# SCH_IntegratedAvionics_Mk_1_2024-03-19.net
KiCad netlist of a schematic drawn in EasyEDA
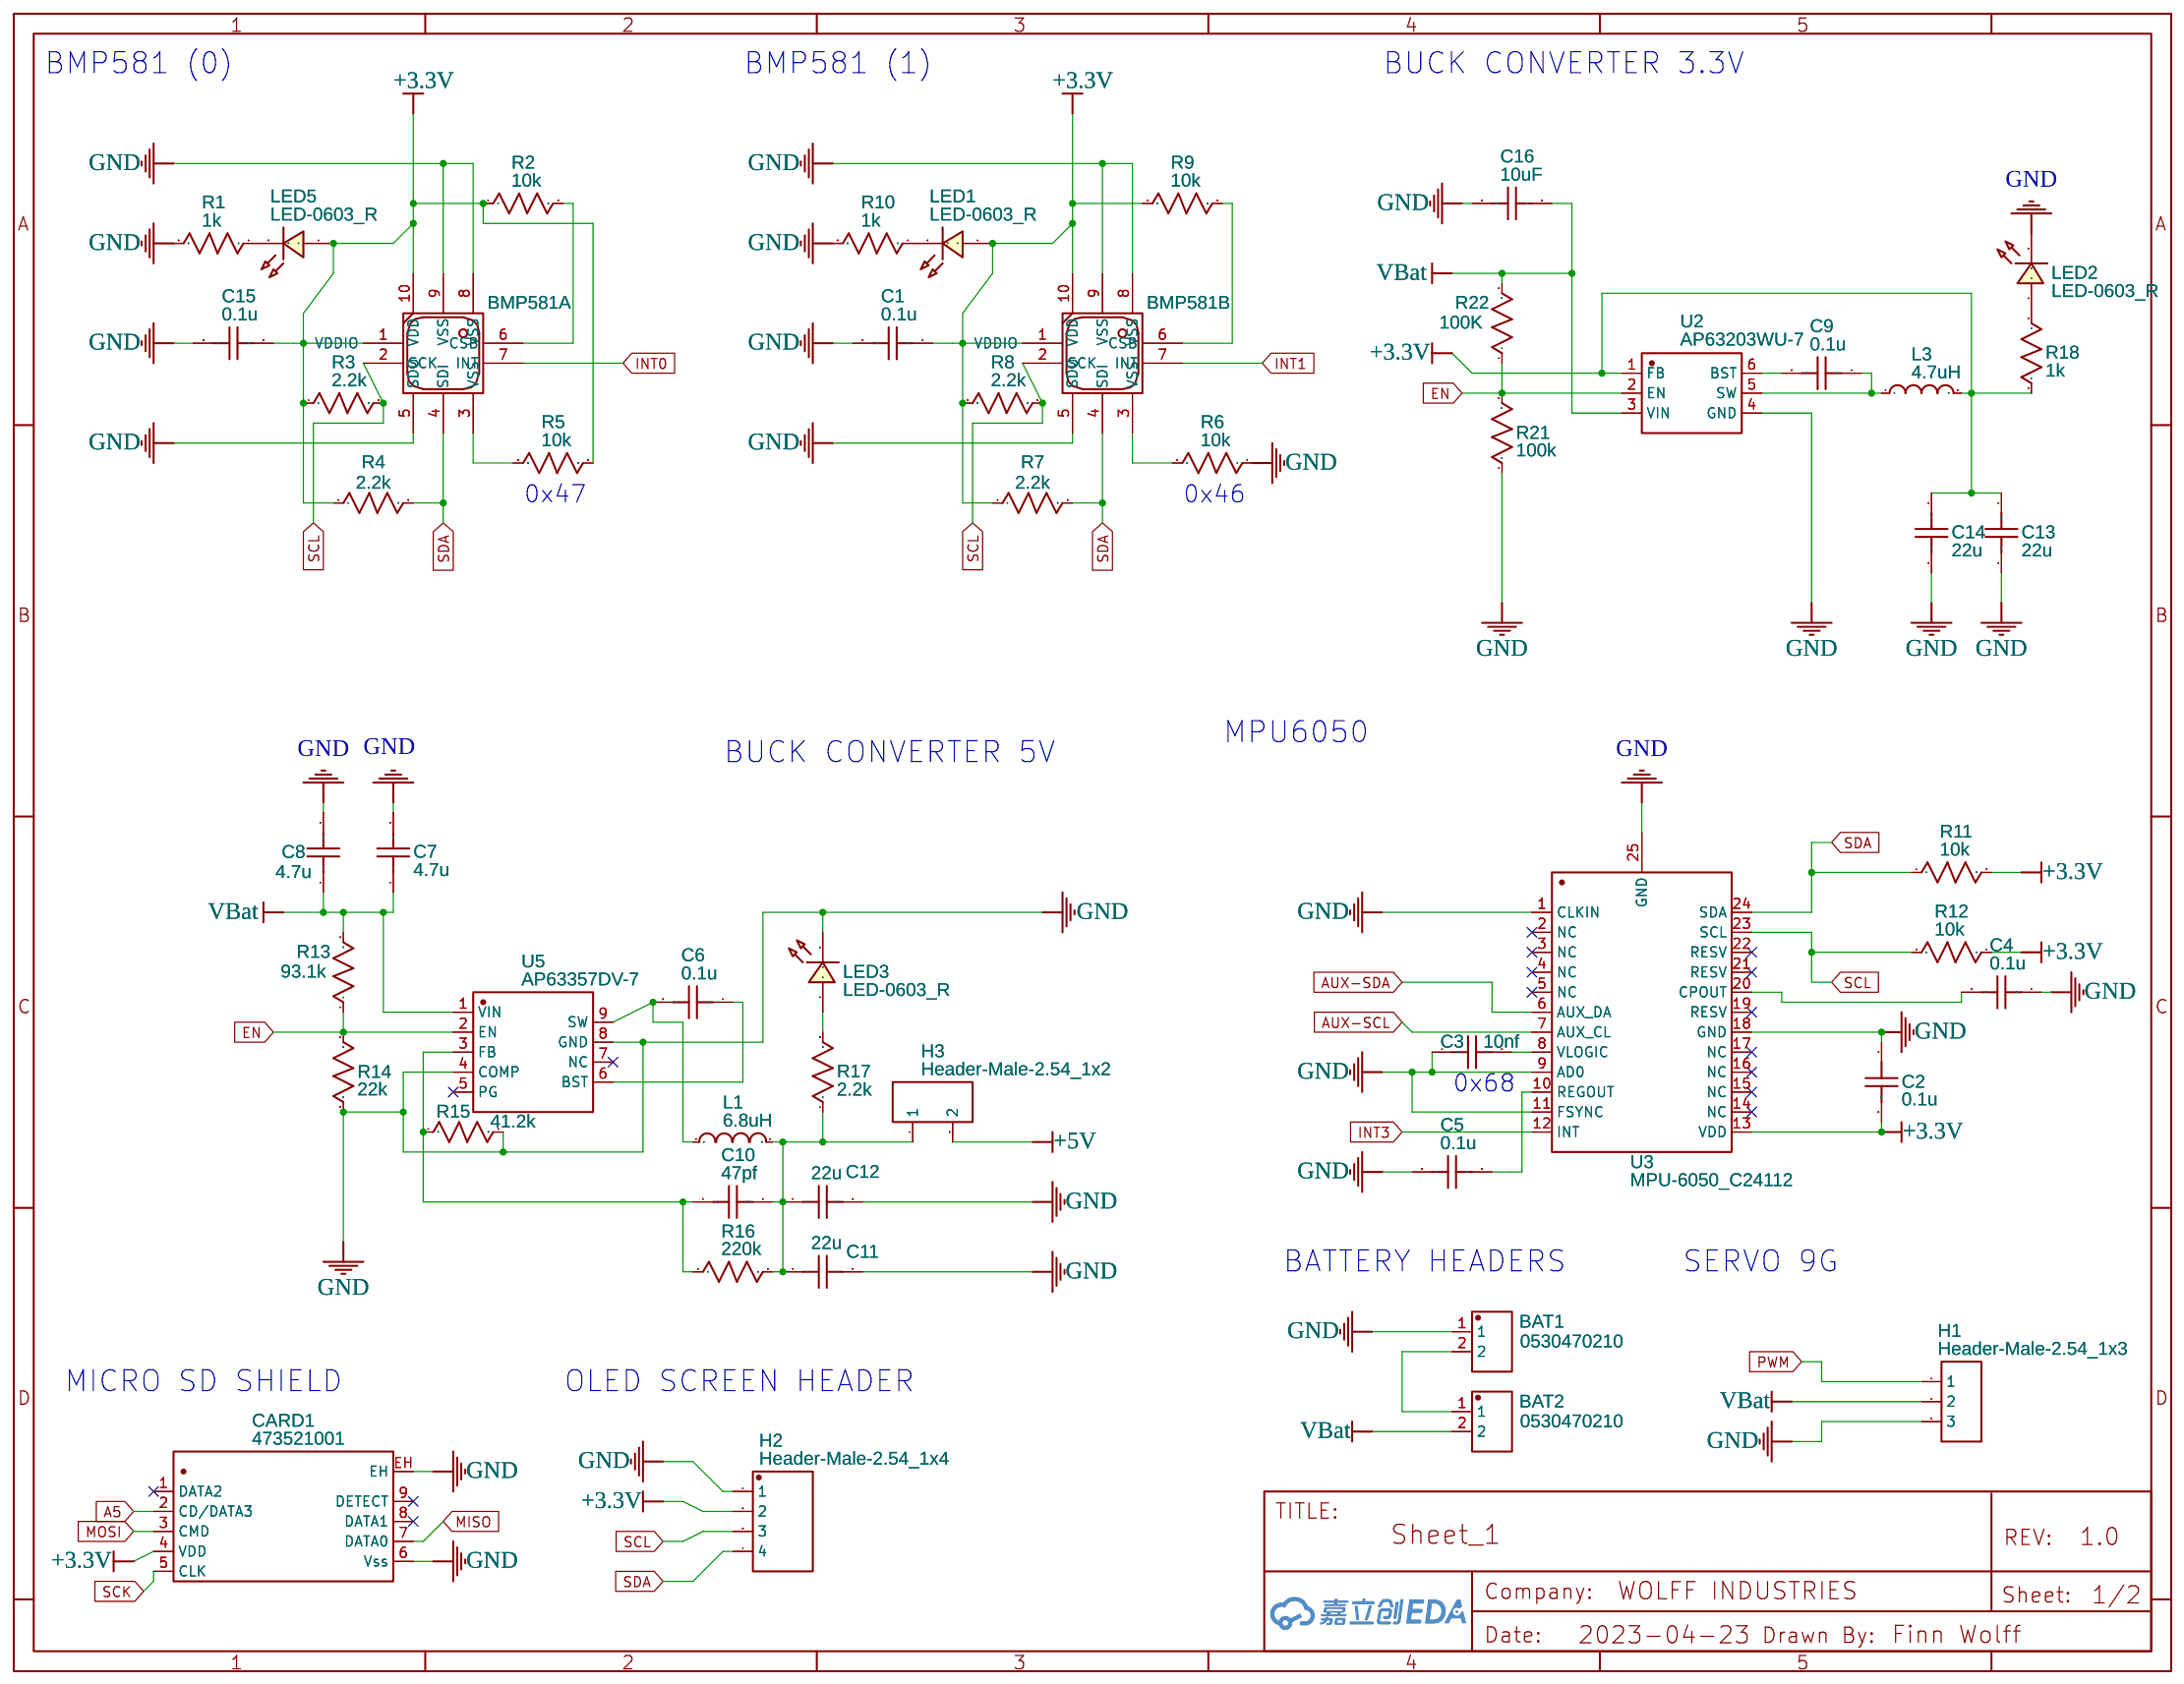
[diagram p0: Sheet_1SEN]
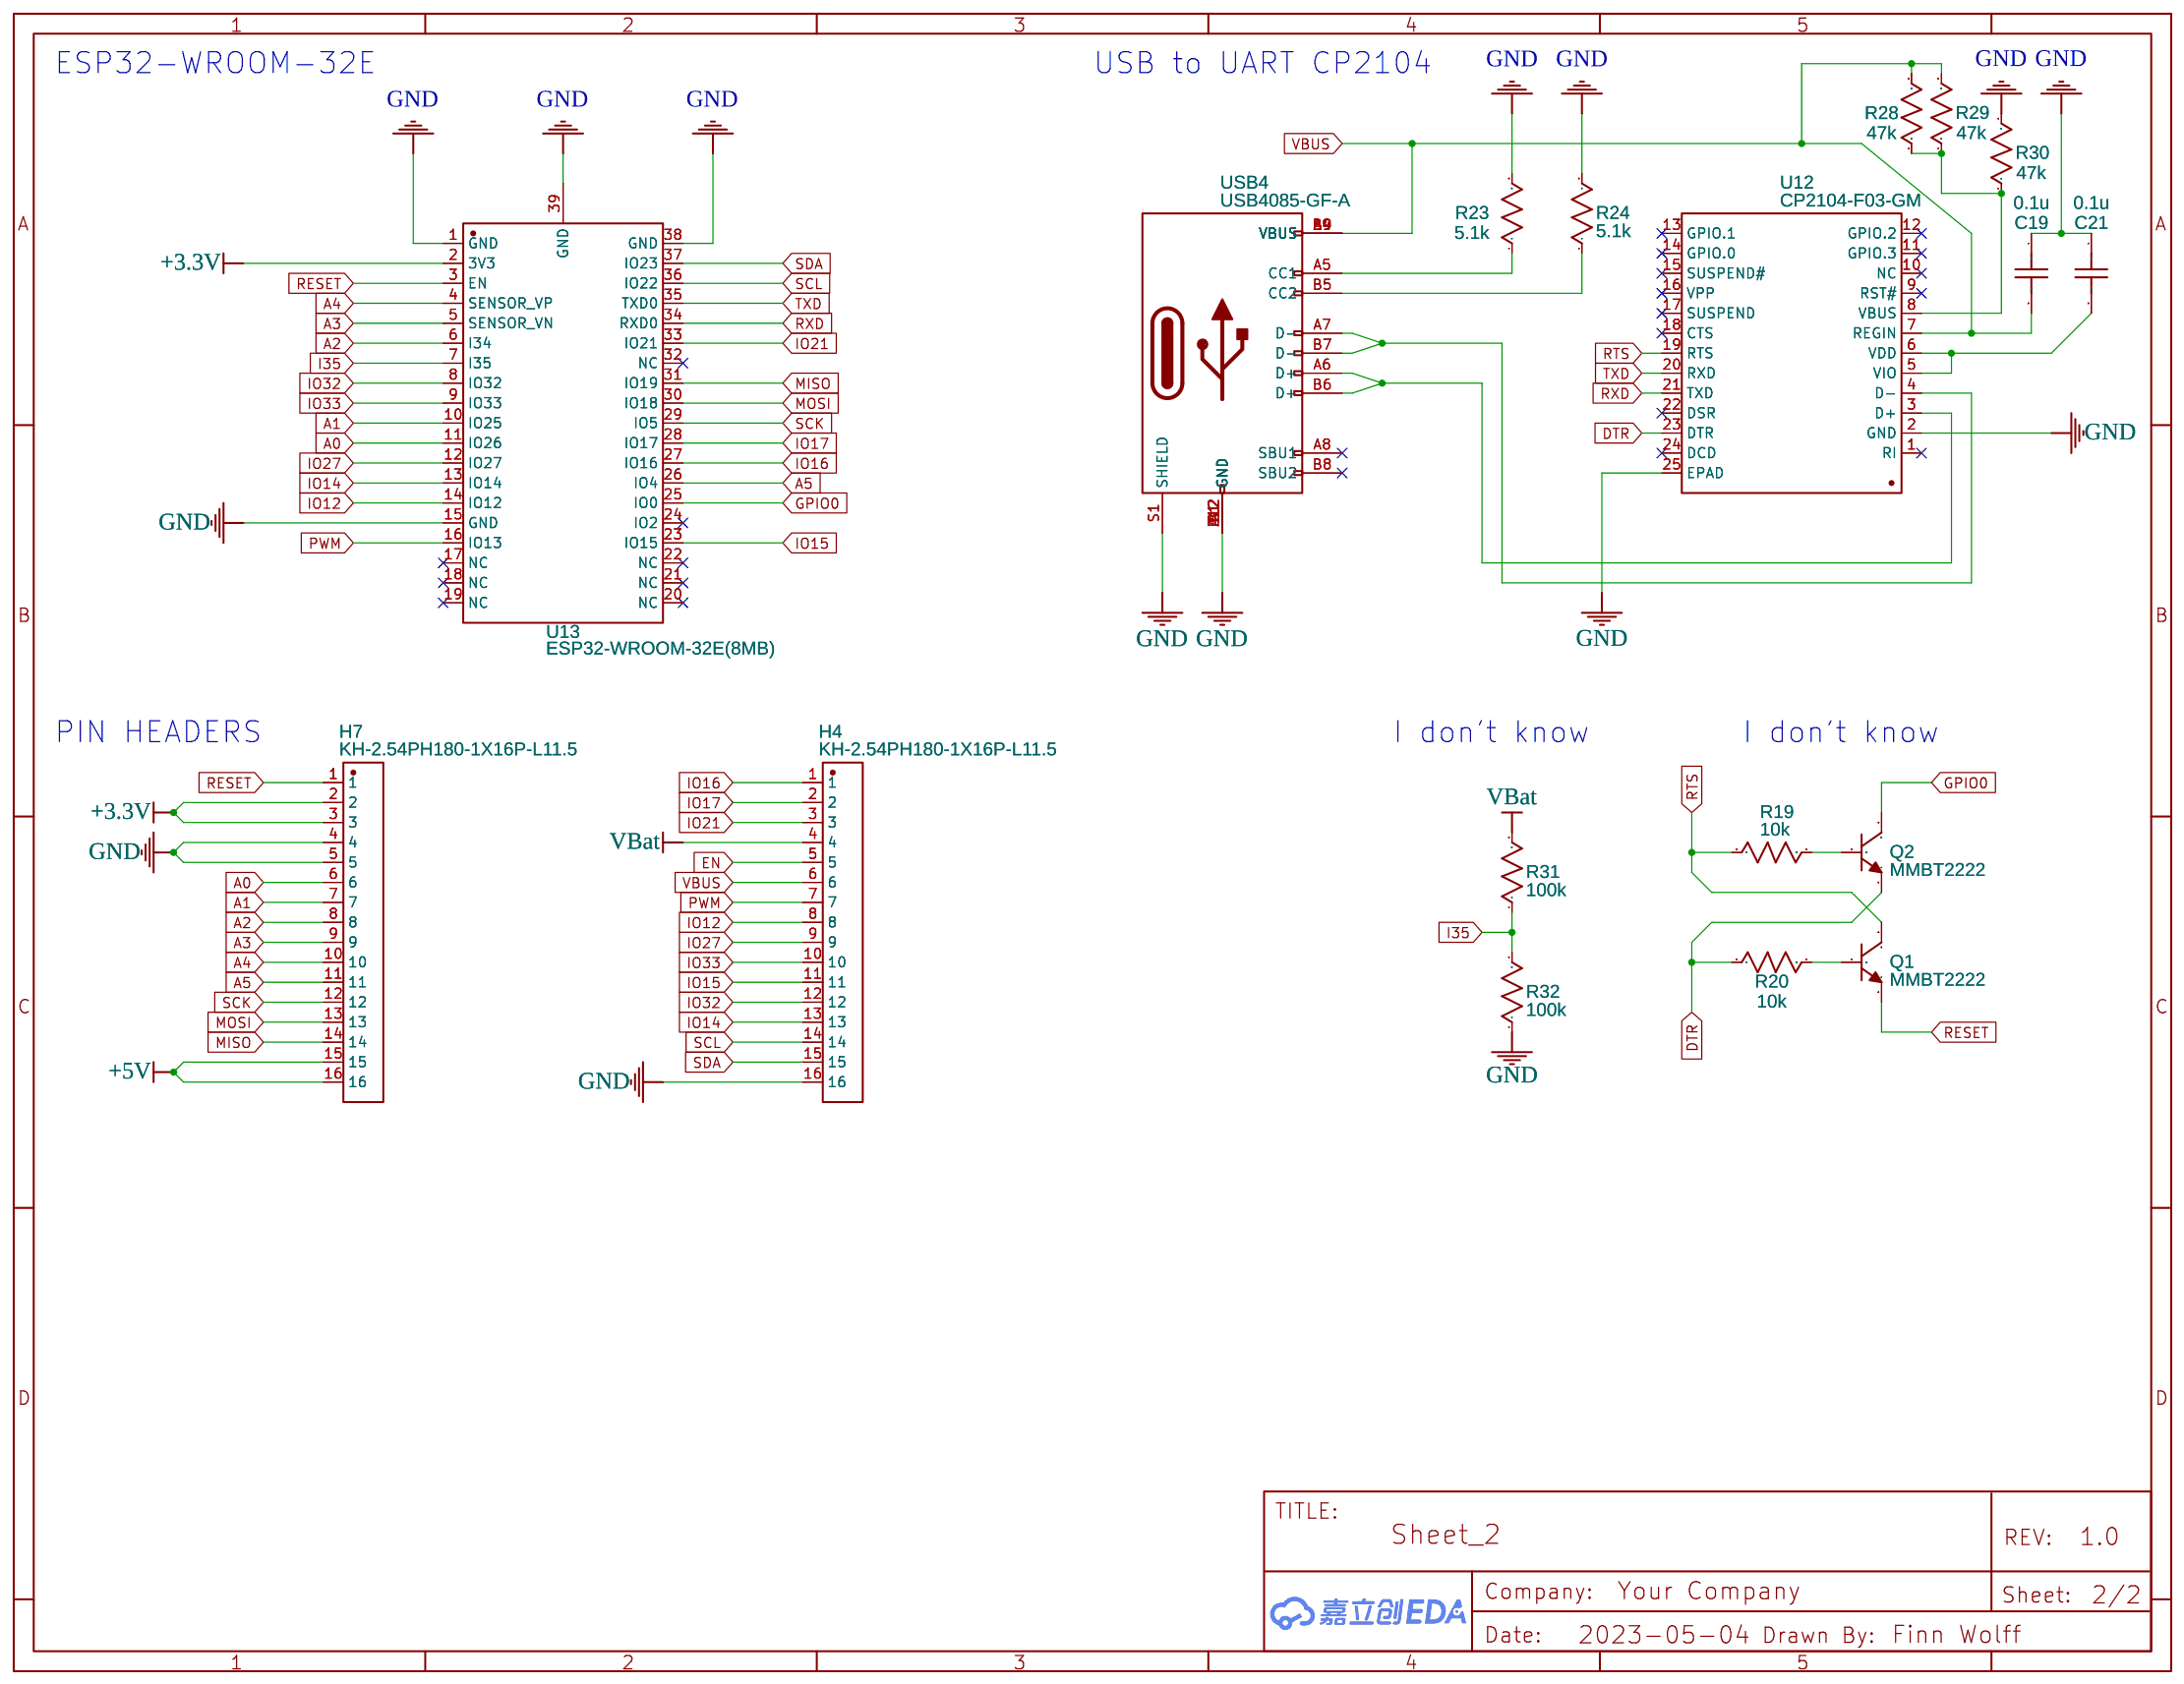
[diagram p1: Sheet_2ESP]

(export (version "E")
  (design (tool "Eeschema 10.0.6"))
  (components
    (comp (ref "BAT1")
      (value "0530470210")
      (fields (field (name "BOM_Supplier Part") "C114130"))
      (libsource (lib "") (part "0530470210"))
    )
    (comp (ref "BAT2")
      (value "0530470210")
      (fields (field (name "BOM_Supplier Part") "C114130"))
      (libsource (lib "") (part "0530470210"))
    )
    (comp (ref "C1")
      (value "0.1u")
      (fields (field (name "Manufacturer Part") "0402B104K160CT"))
      (libsource (lib "") (part "0402B104K160CT"))
    )
    (comp (ref "C2")
      (value "0.1u")
      (fields (field (name "Manufacturer Part") "0402B104K160CT"))
      (libsource (lib "") (part "0402B104K160CT_1"))
    )
    (comp (ref "C3") (value "10nf") (libsource (lib "") (part "C_0603_US")))
    (comp (ref "C4")
      (value "0.1u")
      (fields (field (name "Manufacturer Part") "0402B104K160CT"))
      (libsource (lib "") (part "0402B104K160CT"))
    )
    (comp (ref "C5")
      (value "0.1u")
      (fields (field (name "Manufacturer Part") "0402B104K160CT"))
      (libsource (lib "") (part "0402B104K160CT"))
    )
    (comp (ref "C6")
      (value "0.1u")
      (fields (field (name "Manufacturer Part") "0402B104K160CT"))
      (libsource (lib "") (part "0402B104K160CT"))
    )
    (comp (ref "C7") (value "4.7u") (libsource (lib "") (part "C_0603_US_2")))
    (comp (ref "C8") (value "4.7u") (libsource (lib "") (part "C_0603_US_2")))
    (comp (ref "C9")
      (value "0.1u")
      (fields (field (name "Manufacturer Part") "0402B104K160CT"))
      (libsource (lib "") (part "0402B104K160CT"))
    )
    (comp (ref "C10") (value "47pf") (libsource (lib "") (part "C_0603_US")))
    (comp (ref "C11") (value "22u") (libsource (lib "") (part "C_0603_US")))
    (comp (ref "C12") (value "22u") (libsource (lib "") (part "C_0603_US")))
    (comp (ref "C13") (value "22u") (libsource (lib "") (part "C_0603_US_1")))
    (comp (ref "C14") (value "22u") (libsource (lib "") (part "C_0603_US_1")))
    (comp (ref "C15")
      (value "0.1u")
      (fields (field (name "Manufacturer Part") "0402B104K160CT"))
      (libsource (lib "") (part "0402B104K160CT"))
    )
    (comp (ref "C16")
      (value "10uF")
      (fields
        (field (name "Manufacturer Part") "CL32A106KA9LNNE")
        (field (name "Manufacturer") "SAMSUNG(三星)")
      )
      (libsource (lib "") (part "CL32A106KA9LNNE"))
    )
    (comp (ref "CARD1")
      (value "473521001")
      (fields (field (name "BOM_Supplier Part") "C293569"))
      (libsource (lib "") (part "473521001"))
    )
    (comp (ref "H1")
      (value "Header-Male-2.54_1x3")
      (fields (field (name "BOM_Manufacturer Part") "2.54-1*3P针") (field (name "BOM_Supplier Part") "C49257"))
      (libsource (lib "") (part "Header-Male-2.54_1x3"))
    )
    (comp (ref "H2")
      (value "Header-Male-2.54_1x4")
      (fields
        (field (name "BOM_Manufacturer Part") "B-2100S04P-A110")
        (field (name "BOM_Supplier Part") "C124378")
      )
      (libsource (lib "") (part "Header-Male-2.54_1x4"))
    )
    (comp (ref "H3")
      (value "Header-Male-2.54_1x2")
      (fields (field (name "BOM_Manufacturer Part") "826629-2") (field (name "BOM_Supplier Part") "C86471"))
      (libsource (lib "") (part "Header-Male-2.54_1x2"))
    )
    (comp (ref "L1")
      (value "6.8uH")
      (fields
        (field (name "Manufacturer Part") "HPC5040NF-6R8M")
        (field (name "Manufacturer") "TAI-TECH(台庆)")
      )
      (libsource (lib "") (part "HPC5040NF-6R8M"))
    )
    (comp (ref "L3")
      (value "4.7uH")
      (fields
        (field (name "Manufacturer Part") "NRS5020T4R7MMGJ")
        (field (name "Manufacturer") "TAIYO YUDEN(太诱)")
      )
      (libsource (lib "") (part "NRS5020T4R7MMGJ"))
    )
    (comp (ref "LED1")
      (value "LED-0603_R")
      (fields
        (field (name "BOM_Manufacturer Part") "19-217/R6C-AL1M2VY/3T")
        (field (name "BOM_Supplier Part") "C72044")
      )
      (libsource (lib "") (part "LED-0603_R"))
    )
    (comp (ref "LED2")
      (value "LED-0603_R")
      (fields
        (field (name "BOM_Manufacturer Part") "19-217/R6C-AL1M2VY/3T")
        (field (name "BOM_Supplier Part") "C72044")
      )
      (libsource (lib "") (part "LED-0603_R_1"))
    )
    (comp (ref "LED3")
      (value "LED-0603_R")
      (fields
        (field (name "BOM_Manufacturer Part") "19-217/R6C-AL1M2VY/3T")
        (field (name "BOM_Supplier Part") "C72044")
      )
      (libsource (lib "") (part "LED-0603_R_1"))
    )
    (comp (ref "LED5")
      (value "LED-0603_R")
      (fields
        (field (name "BOM_Manufacturer Part") "19-217/R6C-AL1M2VY/3T")
        (field (name "BOM_Supplier Part") "C72044")
      )
      (libsource (lib "") (part "LED-0603_R"))
    )
    (comp (ref "R1") (value "1k") (libsource (lib "") (part "R_0603_US_2")))
    (comp (ref "R2") (value "10k") (libsource (lib "") (part "R_0603_US")))
    (comp (ref "R3") (value "2.2k") (libsource (lib "") (part "R_0603_US")))
    (comp (ref "R4") (value "2.2k") (libsource (lib "") (part "R_0603_US")))
    (comp (ref "R5") (value "10k") (libsource (lib "") (part "R_0603_US_2")))
    (comp (ref "R6") (value "10k") (libsource (lib "") (part "R_0603_US_2")))
    (comp (ref "R7") (value "2.2k") (libsource (lib "") (part "R_0603_US")))
    (comp (ref "R8") (value "2.2k") (libsource (lib "") (part "R_0603_US")))
    (comp (ref "R9") (value "10k") (libsource (lib "") (part "R_0603_US")))
    (comp (ref "R10") (value "1k") (libsource (lib "") (part "R_0603_US_2")))
    (comp (ref "R11") (value "10k") (libsource (lib "") (part "R_0603_US")))
    (comp (ref "R12") (value "10k") (libsource (lib "") (part "R_0603_US_2")))
    (comp (ref "R13") (value "93.1k") (libsource (lib "") (part "R_0603_US_1")))
    (comp (ref "R14") (value "22k") (libsource (lib "") (part "R_0603_US_1")))
    (comp (ref "R15") (value "41.2k") (libsource (lib "") (part "R_0603_US")))
    (comp (ref "R16") (value "220k") (libsource (lib "") (part "R_0603_US")))
    (comp (ref "R17") (value "2.2k") (libsource (lib "") (part "R_0603_US_1")))
    (comp (ref "R18") (value "1k") (libsource (lib "") (part "R_0603_US_1")))
    (comp (ref "R21") (value "100k") (libsource (lib "") (part "R_0603_US_1")))
    (comp (ref "R22") (value "100K") (libsource (lib "") (part "R_0603_US_1")))
    (comp (ref "U1")
      (value "BMP581A")
      (fields
        (field (name "BOM_Manufacturer Part") "BMP581")
        (field (name "BOM_Supplier Part") "BMP581CT-ND")
      )
      (libsource (lib "") (part "BMP581"))
    )
    (comp (ref "U2")
      (value "AP63203WU-7")
      (fields (field (name "Manufacturer") "DIODES(美台)"))
      (libsource (lib "") (part "AP63203WU-7"))
    )
    (comp (ref "U3")
      (value "MPU-6050_C24112")
      (fields (field (name "BOM_Manufacturer Part") "MPU-6050") (field (name "BOM_Supplier Part") "C24112"))
      (libsource (lib "") (part "MPU-6050_C24112"))
    )
    (comp (ref "U4")
      (value "BMP581B")
      (fields
        (field (name "BOM_Manufacturer Part") "BMP581")
        (field (name "BOM_Supplier Part") "BMP581CT-ND")
      )
      (libsource (lib "") (part "BMP581"))
    )
    (comp (ref "U5")
      (value "AP63357DV-7")
      (fields (field (name "BOM_Supplier Part") "C2158014"))
      (libsource (lib "") (part "AP63357DV-7"))
    )
    (comp (ref "C19") (value "0.1u") (libsource (lib "") (part "C_0603_US")))
    (comp (ref "C21") (value "0.1u") (libsource (lib "") (part "C_0603_US")))
    (comp (ref "H4")
      (value "KH-2.54PH180-1X16P-L11.5")
      (fields (field (name "Manufacturer") "kinghelm(金航标)"))
      (libsource (lib "") (part "KH-2.54PH180-1X16P-L11.5"))
    )
    (comp (ref "H7")
      (value "KH-2.54PH180-1X16P-L11.5")
      (fields (field (name "Manufacturer") "kinghelm(金航标)"))
      (libsource (lib "") (part "KH-2.54PH180-1X16P-L11.5"))
    )
    (comp (ref "Q1")
      (value "MMBT2222")
      (fields (field (name "Manufacturer") "YONGYUTAI(永裕泰)"))
      (libsource (lib "") (part "MMBT2222"))
    )
    (comp (ref "Q2")
      (value "MMBT2222")
      (fields (field (name "Manufacturer") "YONGYUTAI(永裕泰)"))
      (libsource (lib "") (part "MMBT2222"))
    )
    (comp (ref "R19") (value "10k") (libsource (lib "") (part "R_0603_US")))
    (comp (ref "R20") (value "10k") (libsource (lib "") (part "R_0603_US")))
    (comp (ref "R23") (value "5.1k") (libsource (lib "") (part "R_0603_US_1")))
    (comp (ref "R24") (value "5.1k") (libsource (lib "") (part "R_0603_US_1")))
    (comp (ref "R28") (value "47k") (libsource (lib "") (part "R_0603_US_1")))
    (comp (ref "R29") (value "47k") (libsource (lib "") (part "R_0603_US_1")))
    (comp (ref "R30") (value "47k") (libsource (lib "") (part "R_0603_US_1")))
    (comp (ref "R31") (value "100k") (libsource (lib "") (part "R_0603_US_1")))
    (comp (ref "R32") (value "100k") (libsource (lib "") (part "R_0603_US_1")))
    (comp (ref "U12")
      (value "CP2104-F03-GM")
      (fields
        (field (name "BOM_Manufacturer Part") "CP2104-F03-GMR")
        (field (name "BOM_Supplier Part") "C47742")
      )
      (libsource (lib "") (part "CP2104-F03-GM"))
    )
    (comp (ref "U13")
      (value "ESP32-WROOM-32E(8MB)")
      (fields
        (field (name "BOM_Manufacturer Part") "ESP32-WROOM-32E-N8")
        (field (name "BOM_Supplier Part") "C701342")
      )
      (libsource (lib "") (part "ESP32-WROOM-32E(8MB)"))
    )
    (comp (ref "USB4")
      (value "USB4085-GF-A")
      (fields (field (name "BOM_Supplier Part") "C9900013983"))
      (libsource (lib "") (part "USB4085-GF-A"))
    )
  )
  (nets
    (net (code "1") (name "+3.3V") (class "Default")
      (node (ref "C1") (pin "1") (pinfunction "1_1") (pintype "unspecified"))
      (node (ref "C13") (pin "1") (pinfunction "1_1") (pintype "unspecified"))
      (node (ref "C14") (pin "1") (pinfunction "1_1") (pintype "unspecified"))
      (node (ref "C15") (pin "1") (pinfunction "1_1") (pintype "unspecified"))
      (node (ref "C2") (pin "2") (pinfunction "2_2") (pintype "unspecified"))
      (node (ref "CARD1") (pin "4") (pinfunction "VDD_4") (pintype "unspecified"))
      (node (ref "H2") (pin "2") (pinfunction "2_2") (pintype "unspecified"))
      (node (ref "H7") (pin "2") (pinfunction "2_2") (pintype "unspecified"))
      (node (ref "H7") (pin "3") (pinfunction "3_3") (pintype "unspecified"))
      (node (ref "L3") (pin "2") (pinfunction "2_2") (pintype "unspecified"))
      (node (ref "LED1") (pin "1") (pinfunction "1_1") (pintype "unspecified"))
      (node (ref "LED5") (pin "1") (pinfunction "1_1") (pintype "unspecified"))
      (node (ref "R11") (pin "2") (pinfunction "2_2") (pintype "unspecified"))
      (node (ref "R12") (pin "1") (pinfunction "1_1") (pintype "unspecified"))
      (node (ref "R18") (pin "1") (pinfunction "1_1") (pintype "unspecified"))
      (node (ref "R2") (pin "1") (pinfunction "1_1") (pintype "unspecified"))
      (node (ref "R3") (pin "1") (pinfunction "1_1") (pintype "unspecified"))
      (node (ref "R4") (pin "1") (pinfunction "1_1") (pintype "unspecified"))
      (node (ref "R5") (pin "1") (pinfunction "1_1") (pintype "unspecified"))
      (node (ref "R7") (pin "1") (pinfunction "1_1") (pintype "unspecified"))
      (node (ref "R8") (pin "1") (pinfunction "1_1") (pintype "unspecified"))
      (node (ref "R9") (pin "1") (pinfunction "1_1") (pintype "unspecified"))
      (node (ref "U1") (pin "10") (pinfunction "VDD_10") (pintype "unspecified"))
      (node (ref "U13") (pin "2") (pinfunction "3V3_2") (pintype "unspecified"))
      (node (ref "U2") (pin "1") (pinfunction "FB_1") (pintype "unspecified"))
      (node (ref "U3") (pin "13") (pinfunction "VDD_13") (pintype "unspecified"))
      (node (ref "U4") (pin "10") (pinfunction "VDD_10") (pintype "unspecified"))
    )
    (net (code "2") (name "+5V") (class "Default")
      (node (ref "H3") (pin "2") (pinfunction "2_2") (pintype "unspecified"))
      (node (ref "H7") (pin "15") (pinfunction "15_15") (pintype "unspecified"))
      (node (ref "H7") (pin "16") (pinfunction "16_16") (pintype "unspecified"))
    )
    (net (code "3") (name "A0") (class "Default")
      (node (ref "H7") (pin "6") (pinfunction "6_6") (pintype "unspecified"))
      (node (ref "U13") (pin "11") (pinfunction "IO26_11") (pintype "unspecified"))
    )
    (net (code "4") (name "A1") (class "Default")
      (node (ref "H7") (pin "7") (pinfunction "7_7") (pintype "unspecified"))
      (node (ref "U13") (pin "10") (pinfunction "IO25_10") (pintype "unspecified"))
    )
    (net (code "5") (name "A2") (class "Default")
      (node (ref "H7") (pin "8") (pinfunction "8_8") (pintype "unspecified"))
      (node (ref "U13") (pin "6") (pinfunction "I34_6") (pintype "unspecified"))
    )
    (net (code "6") (name "A3") (class "Default")
      (node (ref "H7") (pin "9") (pinfunction "9_9") (pintype "unspecified"))
      (node (ref "U13") (pin "5") (pinfunction "SENSOR_VN_5") (pintype "unspecified"))
    )
    (net (code "7") (name "A4") (class "Default")
      (node (ref "H7") (pin "10") (pinfunction "10_10") (pintype "unspecified"))
      (node (ref "U13") (pin "4") (pinfunction "SENSOR_VP_4") (pintype "unspecified"))
    )
    (net (code "8") (name "A5") (class "Default")
      (node (ref "CARD1") (pin "2") (pinfunction "CD/DATA3_2") (pintype "unspecified"))
      (node (ref "H7") (pin "11") (pinfunction "11_11") (pintype "unspecified"))
      (node (ref "U13") (pin "26") (pinfunction "IO4_26") (pintype "unspecified"))
    )
    (net (code "9") (name "AUX-SCL") (class "Default")
      (node (ref "U3") (pin "7") (pinfunction "AUX_CL_7") (pintype "unspecified"))
    )
    (net (code "10") (name "AUX-SDA") (class "Default")
      (node (ref "U3") (pin "6") (pinfunction "AUX_DA_6") (pintype "unspecified"))
    )
    (net (code "11") (name "DTR") (class "Default")
      (node (ref "Q2") (pin "2") (pinfunction "E_2") (pintype "input"))
      (node (ref "R20") (pin "1") (pinfunction "1_1") (pintype "unspecified"))
      (node (ref "U12") (pin "23") (pinfunction "DTR_23") (pintype "unspecified"))
    )
    (net (code "12") (name "EN") (class "Default")
      (node (ref "H4") (pin "5") (pinfunction "5_5") (pintype "unspecified"))
      (node (ref "R13") (pin "1") (pinfunction "1_1") (pintype "unspecified"))
      (node (ref "R14") (pin "2") (pinfunction "2_2") (pintype "unspecified"))
      (node (ref "R21") (pin "2") (pinfunction "2_2") (pintype "unspecified"))
      (node (ref "R22") (pin "1") (pinfunction "1_1") (pintype "unspecified"))
      (node (ref "U2") (pin "2") (pinfunction "EN_2") (pintype "unspecified"))
      (node (ref "U5") (pin "2") (pinfunction "EN_2") (pintype "unspecified"))
    )
    (net (code "13") (name "GND") (class "Default")
      (node (ref "BAT1") (pin "1") (pinfunction "1_1") (pintype "unspecified"))
      (node (ref "C1") (pin "2") (pinfunction "2_2") (pintype "unspecified"))
      (node (ref "C11") (pin "2") (pinfunction "2_2") (pintype "unspecified"))
      (node (ref "C12") (pin "2") (pinfunction "2_2") (pintype "unspecified"))
      (node (ref "C13") (pin "2") (pinfunction "2_2") (pintype "unspecified"))
      (node (ref "C14") (pin "2") (pinfunction "2_2") (pintype "unspecified"))
      (node (ref "C15") (pin "2") (pinfunction "2_2") (pintype "unspecified"))
      (node (ref "C16") (pin "2") (pinfunction "2_2") (pintype "unspecified"))
      (node (ref "C19") (pin "1") (pinfunction "1_1") (pintype "unspecified"))
      (node (ref "C2") (pin "1") (pinfunction "1_1") (pintype "unspecified"))
      (node (ref "C21") (pin "1") (pinfunction "1_1") (pintype "unspecified"))
      (node (ref "C3") (pin "1") (pinfunction "1_1") (pintype "unspecified"))
      (node (ref "C4") (pin "1") (pinfunction "1_1") (pintype "unspecified"))
      (node (ref "C5") (pin "2") (pinfunction "2_2") (pintype "unspecified"))
      (node (ref "C7") (pin "2") (pinfunction "2_2") (pintype "unspecified"))
      (node (ref "C8") (pin "2") (pinfunction "2_2") (pintype "unspecified"))
      (node (ref "CARD1") (pin "6") (pinfunction "Vss_6") (pintype "unspecified"))
      (node (ref "CARD1") (pin "EH") (pinfunction "EH_EH") (pintype "unspecified"))
      (node (ref "H1") (pin "3") (pinfunction "3_3") (pintype "input"))
      (node (ref "H2") (pin "1") (pinfunction "1_1") (pintype "unspecified"))
      (node (ref "H4") (pin "16") (pinfunction "16_16") (pintype "unspecified"))
      (node (ref "H7") (pin "4") (pinfunction "4_4") (pintype "unspecified"))
      (node (ref "H7") (pin "5") (pinfunction "5_5") (pintype "unspecified"))
      (node (ref "LED2") (pin "2") (pinfunction "2_2") (pintype "unspecified"))
      (node (ref "LED3") (pin "2") (pinfunction "2_2") (pintype "unspecified"))
      (node (ref "R1") (pin "2") (pinfunction "2_2") (pintype "unspecified"))
      (node (ref "R10") (pin "2") (pinfunction "2_2") (pintype "unspecified"))
      (node (ref "R14") (pin "1") (pinfunction "1_1") (pintype "unspecified"))
      (node (ref "R15") (pin "2") (pinfunction "2_2") (pintype "unspecified"))
      (node (ref "R21") (pin "1") (pinfunction "1_1") (pintype "unspecified"))
      (node (ref "R23") (pin "2") (pinfunction "2_2") (pintype "unspecified"))
      (node (ref "R24") (pin "2") (pinfunction "2_2") (pintype "unspecified"))
      (node (ref "R30") (pin "2") (pinfunction "2_2") (pintype "unspecified"))
      (node (ref "R32") (pin "1") (pinfunction "1_1") (pintype "unspecified"))
      (node (ref "R6") (pin "1") (pinfunction "1_1") (pintype "unspecified"))
      (node (ref "U1") (pin "5") (pinfunction "SDO_5") (pintype "unspecified"))
      (node (ref "U1") (pin "8") (pinfunction "VSS_8") (pintype "unspecified"))
      (node (ref "U1") (pin "9") (pinfunction "VSS_9") (pintype "unspecified"))
      (node (ref "U12") (pin "2") (pinfunction "GND_2") (pintype "unspecified"))
      (node (ref "U12") (pin "25") (pinfunction "EPAD_25") (pintype "unspecified"))
      (node (ref "U13") (pin "1") (pinfunction "GND_1") (pintype "unspecified"))
      (node (ref "U13") (pin "15") (pinfunction "GND_15") (pintype "unspecified"))
      (node (ref "U13") (pin "38") (pinfunction "GND_38") (pintype "unspecified"))
      (node (ref "U13") (pin "39") (pinfunction "GND_39") (pintype "unspecified"))
      (node (ref "U2") (pin "4") (pinfunction "GND_4") (pintype "unspecified"))
      (node (ref "U3") (pin "1") (pinfunction "CLKIN_1") (pintype "unspecified"))
      (node (ref "U3") (pin "11") (pinfunction "FSYNC_11") (pintype "unspecified"))
      (node (ref "U3") (pin "18") (pinfunction "GND_18") (pintype "unspecified"))
      (node (ref "U3") (pin "25") (pinfunction "GND_25") (pintype "unspecified"))
      (node (ref "U3") (pin "9") (pinfunction "AD0_9") (pintype "unspecified"))
      (node (ref "U4") (pin "5") (pinfunction "SDO_5") (pintype "unspecified"))
      (node (ref "U4") (pin "8") (pinfunction "VSS_8") (pintype "unspecified"))
      (node (ref "U4") (pin "9") (pinfunction "VSS_9") (pintype "unspecified"))
      (node (ref "U5") (pin "4") (pinfunction "COMP_4") (pintype "unspecified"))
      (node (ref "U5") (pin "8") (pinfunction "GND_8") (pintype "unspecified"))
      (node (ref "USB4") (pin "A1") (pinfunction "GND_A1") (pintype "bidirectional"))
      (node (ref "USB4") (pin "A12") (pinfunction "GND_A12") (pintype "unspecified"))
      (node (ref "USB4") (pin "B1") (pinfunction "GND_B1") (pintype "unspecified"))
      (node (ref "USB4") (pin "B12") (pinfunction "GND_B12") (pintype "unspecified"))
      (node (ref "USB4") (pin "S1") (pinfunction "SHIELD_S1") (pintype "unspecified"))
    )
    (net (code "14") (name "GPIO0") (class "Default")
      (node (ref "Q2") (pin "3") (pinfunction "C_3") (pintype "input"))
      (node (ref "U13") (pin "25") (pinfunction "IO0_25") (pintype "unspecified"))
    )
    (net (code "15") (name "I35") (class "Default")
      (node (ref "R31") (pin "1") (pinfunction "1_1") (pintype "unspecified"))
      (node (ref "R32") (pin "2") (pinfunction "2_2") (pintype "unspecified"))
      (node (ref "U13") (pin "7") (pinfunction "I35_7") (pintype "unspecified"))
    )
    (net (code "16") (name "INT0") (class "Default")
      (node (ref "U1") (pin "7") (pinfunction "INT_7") (pintype "unspecified"))
    )
    (net (code "17") (name "INT1") (class "Default")
      (node (ref "U4") (pin "7") (pinfunction "INT_7") (pintype "unspecified"))
    )
    (net (code "18") (name "INT3") (class "Default")
      (node (ref "U3") (pin "12") (pinfunction "INT_12") (pintype "unspecified"))
    )
    (net (code "19") (name "IO12") (class "Default")
      (node (ref "H4") (pin "8") (pinfunction "8_8") (pintype "unspecified"))
      (node (ref "U13") (pin "14") (pinfunction "IO12_14") (pintype "unspecified"))
    )
    (net (code "20") (name "IO14") (class "Default")
      (node (ref "H4") (pin "13") (pinfunction "13_13") (pintype "unspecified"))
      (node (ref "U13") (pin "13") (pinfunction "IO14_13") (pintype "unspecified"))
    )
    (net (code "21") (name "IO15") (class "Default")
      (node (ref "H4") (pin "11") (pinfunction "11_11") (pintype "unspecified"))
      (node (ref "U13") (pin "23") (pinfunction "IO15_23") (pintype "unspecified"))
    )
    (net (code "22") (name "IO16") (class "Default")
      (node (ref "H4") (pin "1") (pinfunction "1_1") (pintype "unspecified"))
      (node (ref "U13") (pin "27") (pinfunction "IO16_27") (pintype "unspecified"))
    )
    (net (code "23") (name "IO17") (class "Default")
      (node (ref "H4") (pin "2") (pinfunction "2_2") (pintype "unspecified"))
      (node (ref "U13") (pin "28") (pinfunction "IO17_28") (pintype "unspecified"))
    )
    (net (code "24") (name "IO21") (class "Default")
      (node (ref "H4") (pin "3") (pinfunction "3_3") (pintype "unspecified"))
      (node (ref "U13") (pin "33") (pinfunction "IO21_33") (pintype "unspecified"))
    )
    (net (code "25") (name "IO27") (class "Default")
      (node (ref "H4") (pin "9") (pinfunction "9_9") (pintype "unspecified"))
      (node (ref "U13") (pin "12") (pinfunction "IO27_12") (pintype "unspecified"))
    )
    (net (code "26") (name "IO32") (class "Default")
      (node (ref "H4") (pin "12") (pinfunction "12_12") (pintype "unspecified"))
      (node (ref "U13") (pin "8") (pinfunction "IO32_8") (pintype "unspecified"))
    )
    (net (code "27") (name "IO33") (class "Default")
      (node (ref "H4") (pin "10") (pinfunction "10_10") (pintype "unspecified"))
      (node (ref "U13") (pin "9") (pinfunction "IO33_9") (pintype "unspecified"))
    )
    (net (code "28") (name "MISO") (class "Default")
      (node (ref "CARD1") (pin "7") (pinfunction "DATA0_7") (pintype "unspecified"))
      (node (ref "H7") (pin "14") (pinfunction "14_14") (pintype "unspecified"))
      (node (ref "U13") (pin "31") (pinfunction "IO19_31") (pintype "unspecified"))
    )
    (net (code "29") (name "MOSI") (class "Default")
      (node (ref "CARD1") (pin "3") (pinfunction "CMD_3") (pintype "unspecified"))
      (node (ref "H7") (pin "13") (pinfunction "13_13") (pintype "unspecified"))
      (node (ref "U13") (pin "30") (pinfunction "IO18_30") (pintype "unspecified"))
    )
    (net (code "30") (name "Net-(BAT1-Pad2)") (class "Default")
      (node (ref "BAT1") (pin "2") (pinfunction "2_2") (pintype "unspecified"))
      (node (ref "BAT2") (pin "1") (pinfunction "1_1") (pintype "unspecified"))
    )
    (net (code "31") (name "Net-(C10-Pad2)") (class "Default")
      (node (ref "C10") (pin "2") (pinfunction "2_2") (pintype "unspecified"))
      (node (ref "C11") (pin "1") (pinfunction "1_1") (pintype "unspecified"))
      (node (ref "C12") (pin "1") (pinfunction "1_1") (pintype "unspecified"))
      (node (ref "H3") (pin "1") (pinfunction "1_1") (pintype "unspecified"))
      (node (ref "L1") (pin "2") (pinfunction "2_2") (pintype "unspecified"))
      (node (ref "R16") (pin "2") (pinfunction "2_2") (pintype "unspecified"))
      (node (ref "R17") (pin "1") (pinfunction "1_1") (pintype "unspecified"))
    )
    (net (code "32") (name "Net-(LED1-Pad2)") (class "Default")
      (node (ref "LED1") (pin "2") (pinfunction "2_2") (pintype "unspecified"))
      (node (ref "R10") (pin "1") (pinfunction "1_1") (pintype "unspecified"))
    )
    (net (code "33") (name "Net-(LED2-Pad1)") (class "Default")
      (node (ref "LED2") (pin "1") (pinfunction "1_1") (pintype "unspecified"))
      (node (ref "R18") (pin "2") (pinfunction "2_2") (pintype "unspecified"))
    )
    (net (code "34") (name "Net-(LED3-Pad1)") (class "Default")
      (node (ref "LED3") (pin "1") (pinfunction "1_1") (pintype "unspecified"))
      (node (ref "R17") (pin "2") (pinfunction "2_2") (pintype "unspecified"))
    )
    (net (code "35") (name "Net-(LED5-Pad2)") (class "Default")
      (node (ref "LED5") (pin "2") (pinfunction "2_2") (pintype "unspecified"))
      (node (ref "R1") (pin "1") (pinfunction "1_1") (pintype "unspecified"))
    )
    (net (code "36") (name "Net-(Q1-B)") (class "Default")
      (node (ref "Q1") (pin "1") (pinfunction "B_1") (pintype "input"))
      (node (ref "R20") (pin "2") (pinfunction "2_2") (pintype "unspecified"))
    )
    (net (code "37") (name "Net-(Q2-B)") (class "Default")
      (node (ref "Q2") (pin "1") (pinfunction "B_1") (pintype "input"))
      (node (ref "R19") (pin "2") (pinfunction "2_2") (pintype "unspecified"))
    )
    (net (code "38") (name "Net-(R5-Pad2)") (class "Default")
      (node (ref "R5") (pin "2") (pinfunction "2_2") (pintype "unspecified"))
      (node (ref "U1") (pin "3") (pinfunction "VSS_3") (pintype "unspecified"))
    )
    (net (code "39") (name "Net-(R6-Pad2)") (class "Default")
      (node (ref "R6") (pin "2") (pinfunction "2_2") (pintype "unspecified"))
      (node (ref "U4") (pin "3") (pinfunction "VSS_3") (pintype "unspecified"))
    )
    (net (code "40") (name "Net-(U1-CSB)") (class "Default")
      (node (ref "R2") (pin "2") (pinfunction "2_2") (pintype "unspecified"))
      (node (ref "U1") (pin "6") (pinfunction "CSB_6") (pintype "unspecified"))
    )
    (net (code "41") (name "Net-(U2-BST)") (class "Default")
      (node (ref "C9") (pin "2") (pinfunction "2_2") (pintype "unspecified"))
      (node (ref "U2") (pin "6") (pinfunction "BST_6") (pintype "unspecified"))
    )
    (net (code "42") (name "Net-(U2-SW)") (class "Default")
      (node (ref "C9") (pin "1") (pinfunction "1_1") (pintype "unspecified"))
      (node (ref "L3") (pin "1") (pinfunction "1_1") (pintype "unspecified"))
      (node (ref "U2") (pin "5") (pinfunction "SW_5") (pintype "unspecified"))
    )
    (net (code "43") (name "Net-(U3-CPOUT)") (class "Default")
      (node (ref "C4") (pin "2") (pinfunction "2_2") (pintype "unspecified"))
      (node (ref "U3") (pin "20") (pinfunction "CPOUT_20") (pintype "unspecified"))
    )
    (net (code "44") (name "Net-(U3-REGOUT)") (class "Default")
      (node (ref "C5") (pin "1") (pinfunction "1_1") (pintype "unspecified"))
      (node (ref "U3") (pin "10") (pinfunction "REGOUT_10") (pintype "unspecified"))
    )
    (net (code "45") (name "Net-(U3-VLOGIC)") (class "Default")
      (node (ref "C3") (pin "2") (pinfunction "2_2") (pintype "unspecified"))
      (node (ref "U3") (pin "8") (pinfunction "VLOGIC_8") (pintype "unspecified"))
    )
    (net (code "46") (name "Net-(U4-CSB)") (class "Default")
      (node (ref "R9") (pin "2") (pinfunction "2_2") (pintype "unspecified"))
      (node (ref "U4") (pin "6") (pinfunction "CSB_6") (pintype "unspecified"))
    )
    (net (code "47") (name "Net-(U5-BST)") (class "Default")
      (node (ref "C6") (pin "1") (pinfunction "1_1") (pintype "unspecified"))
      (node (ref "U5") (pin "6") (pinfunction "BST_6") (pintype "unspecified"))
    )
    (net (code "48") (name "Net-(U5-FB)") (class "Default")
      (node (ref "C10") (pin "1") (pinfunction "1_1") (pintype "unspecified"))
      (node (ref "R15") (pin "1") (pinfunction "1_1") (pintype "unspecified"))
      (node (ref "R16") (pin "1") (pinfunction "1_1") (pintype "unspecified"))
      (node (ref "U5") (pin "3") (pinfunction "FB_3") (pintype "unspecified"))
    )
    (net (code "49") (name "Net-(U5-SW)") (class "Default")
      (node (ref "C6") (pin "2") (pinfunction "2_2") (pintype "unspecified"))
      (node (ref "L1") (pin "1") (pinfunction "1_1") (pintype "unspecified"))
      (node (ref "U5") (pin "9") (pinfunction "SW_9") (pintype "unspecified"))
    )
    (net (code "50") (name "Net-(U12-D+)") (class "Default")
      (node (ref "U12") (pin "3") (pinfunction "D+_3") (pintype "unspecified"))
      (node (ref "USB4") (pin "A6") (pinfunction "D+_A6") (pintype "bidirectional"))
      (node (ref "USB4") (pin "B6") (pinfunction "D+_B6") (pintype "bidirectional"))
    )
    (net (code "51") (name "Net-(U12-D-)") (class "Default")
      (node (ref "U12") (pin "4") (pinfunction "D-_4") (pintype "unspecified"))
      (node (ref "USB4") (pin "A7") (pinfunction "D-_A7") (pintype "bidirectional"))
      (node (ref "USB4") (pin "B7") (pinfunction "D-_B7") (pintype "bidirectional"))
    )
    (net (code "52") (name "Net-(U12-VBUS)") (class "Default")
      (node (ref "R28") (pin "1") (pinfunction "1_1") (pintype "unspecified"))
      (node (ref "R29") (pin "1") (pinfunction "1_1") (pintype "unspecified"))
      (node (ref "R30") (pin "1") (pinfunction "1_1") (pintype "unspecified"))
      (node (ref "U12") (pin "8") (pinfunction "VBUS_8") (pintype "unspecified"))
    )
    (net (code "53") (name "Net-(U12-VDD)") (class "Default")
      (node (ref "C21") (pin "2") (pinfunction "2_2") (pintype "unspecified"))
      (node (ref "U12") (pin "5") (pinfunction "VIO_5") (pintype "unspecified"))
      (node (ref "U12") (pin "6") (pinfunction "VDD_6") (pintype "unspecified"))
    )
    (net (code "54") (name "Net-(USB4-CC1)") (class "Default")
      (node (ref "R23") (pin "1") (pinfunction "1_1") (pintype "unspecified"))
      (node (ref "USB4") (pin "A5") (pinfunction "CC1_A5") (pintype "bidirectional"))
    )
    (net (code "55") (name "Net-(USB4-CC2)") (class "Default")
      (node (ref "R24") (pin "1") (pinfunction "1_1") (pintype "unspecified"))
      (node (ref "USB4") (pin "B5") (pinfunction "CC2_B5") (pintype "bidirectional"))
    )
    (net (code "56") (name "PWM") (class "Default")
      (node (ref "H1") (pin "1") (pinfunction "1_1") (pintype "input"))
      (node (ref "H4") (pin "7") (pinfunction "7_7") (pintype "unspecified"))
      (node (ref "U13") (pin "16") (pinfunction "IO13_16") (pintype "unspecified"))
    )
    (net (code "57") (name "RESET") (class "Default")
      (node (ref "H7") (pin "1") (pinfunction "1_1") (pintype "unspecified"))
      (node (ref "Q1") (pin "2") (pinfunction "E_2") (pintype "input"))
      (node (ref "U13") (pin "3") (pinfunction "EN_3") (pintype "unspecified"))
    )
    (net (code "58") (name "RTS") (class "Default")
      (node (ref "Q1") (pin "3") (pinfunction "C_3") (pintype "input"))
      (node (ref "R19") (pin "1") (pinfunction "1_1") (pintype "unspecified"))
      (node (ref "U12") (pin "19") (pinfunction "RTS_19") (pintype "unspecified"))
    )
    (net (code "59") (name "RXD") (class "Default")
      (node (ref "U12") (pin "21") (pinfunction "TXD_21") (pintype "unspecified"))
      (node (ref "U13") (pin "34") (pinfunction "RXD0_34") (pintype "unspecified"))
    )
    (net (code "60") (name "SCK") (class "Default")
      (node (ref "CARD1") (pin "5") (pinfunction "CLK_5") (pintype "unspecified"))
      (node (ref "H7") (pin "12") (pinfunction "12_12") (pintype "unspecified"))
      (node (ref "U13") (pin "29") (pinfunction "IO5_29") (pintype "unspecified"))
    )
    (net (code "61") (name "SCL") (class "Default")
      (node (ref "H2") (pin "3") (pinfunction "3_3") (pintype "unspecified"))
      (node (ref "H4") (pin "14") (pinfunction "14_14") (pintype "unspecified"))
      (node (ref "R12") (pin "2") (pinfunction "2_2") (pintype "unspecified"))
      (node (ref "R3") (pin "2") (pinfunction "2_2") (pintype "unspecified"))
      (node (ref "R8") (pin "2") (pinfunction "2_2") (pintype "unspecified"))
      (node (ref "U1") (pin "2") (pinfunction "SCK_2") (pintype "unspecified"))
      (node (ref "U13") (pin "36") (pinfunction "IO22_36") (pintype "unspecified"))
      (node (ref "U3") (pin "23") (pinfunction "SCL_23") (pintype "unspecified"))
      (node (ref "U4") (pin "2") (pinfunction "SCK_2") (pintype "unspecified"))
    )
    (net (code "62") (name "SDA") (class "Default")
      (node (ref "H2") (pin "4") (pinfunction "4_4") (pintype "unspecified"))
      (node (ref "H4") (pin "15") (pinfunction "15_15") (pintype "unspecified"))
      (node (ref "R11") (pin "1") (pinfunction "1_1") (pintype "unspecified"))
      (node (ref "R4") (pin "2") (pinfunction "2_2") (pintype "unspecified"))
      (node (ref "R7") (pin "2") (pinfunction "2_2") (pintype "unspecified"))
      (node (ref "U1") (pin "4") (pinfunction "SDI_4") (pintype "unspecified"))
      (node (ref "U13") (pin "37") (pinfunction "IO23_37") (pintype "unspecified"))
      (node (ref "U3") (pin "24") (pinfunction "SDA_24") (pintype "unspecified"))
      (node (ref "U4") (pin "4") (pinfunction "SDI_4") (pintype "unspecified"))
    )
    (net (code "63") (name "TXD") (class "Default")
      (node (ref "U12") (pin "20") (pinfunction "RXD_20") (pintype "unspecified"))
      (node (ref "U13") (pin "35") (pinfunction "TXD0_35") (pintype "unspecified"))
    )
    (net (code "64") (name "VBUS") (class "Default")
      (node (ref "C19") (pin "2") (pinfunction "2_2") (pintype "unspecified"))
      (node (ref "H4") (pin "6") (pinfunction "6_6") (pintype "unspecified"))
      (node (ref "R28") (pin "2") (pinfunction "2_2") (pintype "unspecified"))
      (node (ref "R29") (pin "2") (pinfunction "2_2") (pintype "unspecified"))
      (node (ref "U12") (pin "7") (pinfunction "REGIN_7") (pintype "unspecified"))
      (node (ref "USB4") (pin "A4") (pinfunction "VBUS_A4") (pintype "bidirectional"))
      (node (ref "USB4") (pin "A9") (pinfunction "VBUS_A9") (pintype "unspecified"))
      (node (ref "USB4") (pin "B4") (pinfunction "VBUS_B4") (pintype "unspecified"))
      (node (ref "USB4") (pin "B9") (pinfunction "VBUS_B9") (pintype "unspecified"))
    )
    (net (code "65") (name "VBat") (class "Default")
      (node (ref "BAT2") (pin "2") (pinfunction "2_2") (pintype "unspecified"))
      (node (ref "C16") (pin "1") (pinfunction "1_1") (pintype "unspecified"))
      (node (ref "C7") (pin "1") (pinfunction "1_1") (pintype "unspecified"))
      (node (ref "C8") (pin "1") (pinfunction "1_1") (pintype "unspecified"))
      (node (ref "H1") (pin "2") (pinfunction "2_2") (pintype "input"))
      (node (ref "H4") (pin "4") (pinfunction "4_4") (pintype "unspecified"))
      (node (ref "R13") (pin "2") (pinfunction "2_2") (pintype "unspecified"))
      (node (ref "R22") (pin "2") (pinfunction "2_2") (pintype "unspecified"))
      (node (ref "R31") (pin "2") (pinfunction "2_2") (pintype "unspecified"))
      (node (ref "U2") (pin "3") (pinfunction "VIN_3") (pintype "unspecified"))
      (node (ref "U5") (pin "1") (pinfunction "VIN_1") (pintype "unspecified"))
    )
    (net (code "66") (name "unconnected-(CARD1-DATA1-Pad8)") (class "Default")
      (node (ref "CARD1") (pin "8") (pinfunction "DATA1_8") (pintype "unspecified+no_connect"))
    )
    (net (code "67") (name "unconnected-(CARD1-DATA2-Pad1)") (class "Default")
      (node (ref "CARD1") (pin "1") (pinfunction "DATA2_1") (pintype "unspecified+no_connect"))
    )
    (net (code "68") (name "unconnected-(CARD1-DETECT-Pad9)") (class "Default")
      (node (ref "CARD1") (pin "9") (pinfunction "DETECT_9") (pintype "unspecified+no_connect"))
    )
    (net (code "69") (name "unconnected-(U1-VDDIO-Pad1)") (class "Default")
      (node (ref "U1") (pin "1") (pinfunction "VDDIO_1") (pintype "unspecified"))
    )
    (net (code "70") (name "unconnected-(U3-NC-Pad2)") (class "Default")
      (node (ref "U3") (pin "2") (pinfunction "NC_2") (pintype "unspecified+no_connect"))
    )
    (net (code "71") (name "unconnected-(U3-NC-Pad3)") (class "Default")
      (node (ref "U3") (pin "3") (pinfunction "NC_3") (pintype "unspecified+no_connect"))
    )
    (net (code "72") (name "unconnected-(U3-NC-Pad4)") (class "Default")
      (node (ref "U3") (pin "4") (pinfunction "NC_4") (pintype "unspecified+no_connect"))
    )
    (net (code "73") (name "unconnected-(U3-NC-Pad5)") (class "Default")
      (node (ref "U3") (pin "5") (pinfunction "NC_5") (pintype "unspecified+no_connect"))
    )
    (net (code "74") (name "unconnected-(U3-NC-Pad14)") (class "Default")
      (node (ref "U3") (pin "14") (pinfunction "NC_14") (pintype "unspecified+no_connect"))
    )
    (net (code "75") (name "unconnected-(U3-NC-Pad15)") (class "Default")
      (node (ref "U3") (pin "15") (pinfunction "NC_15") (pintype "unspecified+no_connect"))
    )
    (net (code "76") (name "unconnected-(U3-NC-Pad16)") (class "Default")
      (node (ref "U3") (pin "16") (pinfunction "NC_16") (pintype "unspecified+no_connect"))
    )
    (net (code "77") (name "unconnected-(U3-NC-Pad17)") (class "Default")
      (node (ref "U3") (pin "17") (pinfunction "NC_17") (pintype "unspecified+no_connect"))
    )
    (net (code "78") (name "unconnected-(U3-RESV-Pad19)") (class "Default")
      (node (ref "U3") (pin "19") (pinfunction "RESV_19") (pintype "unspecified+no_connect"))
    )
    (net (code "79") (name "unconnected-(U3-RESV-Pad21)") (class "Default")
      (node (ref "U3") (pin "21") (pinfunction "RESV_21") (pintype "unspecified+no_connect"))
    )
    (net (code "80") (name "unconnected-(U3-RESV-Pad22)") (class "Default")
      (node (ref "U3") (pin "22") (pinfunction "RESV_22") (pintype "unspecified+no_connect"))
    )
    (net (code "81") (name "unconnected-(U4-VDDIO-Pad1)") (class "Default")
      (node (ref "U4") (pin "1") (pinfunction "VDDIO_1") (pintype "unspecified"))
    )
    (net (code "82") (name "unconnected-(U5-NC-Pad7)") (class "Default")
      (node (ref "U5") (pin "7") (pinfunction "NC_7") (pintype "unspecified+no_connect"))
    )
    (net (code "83") (name "unconnected-(U5-PG-Pad5)") (class "Default")
      (node (ref "U5") (pin "5") (pinfunction "PG_5") (pintype "unspecified+no_connect"))
    )
    (net (code "84") (name "unconnected-(U12-CTS-Pad18)") (class "Default")
      (node (ref "U12") (pin "18") (pinfunction "CTS_18") (pintype "unspecified+no_connect"))
    )
    (net (code "85") (name "unconnected-(U12-DCD-Pad24)") (class "Default")
      (node (ref "U12") (pin "24") (pinfunction "DCD_24") (pintype "unspecified+no_connect"))
    )
    (net (code "86") (name "unconnected-(U12-DSR-Pad22)") (class "Default")
      (node (ref "U12") (pin "22") (pinfunction "DSR_22") (pintype "unspecified+no_connect"))
    )
    (net (code "87") (name "unconnected-(U12-GPIO.0-Pad14)") (class "Default")
      (node (ref "U12") (pin "14") (pinfunction "GPIO.0_14") (pintype "unspecified+no_connect"))
    )
    (net (code "88") (name "unconnected-(U12-GPIO.1-Pad13)") (class "Default")
      (node (ref "U12") (pin "13") (pinfunction "GPIO.1_13") (pintype "unspecified+no_connect"))
    )
    (net (code "89") (name "unconnected-(U12-GPIO.2-Pad12)") (class "Default")
      (node (ref "U12") (pin "12") (pinfunction "GPIO.2_12") (pintype "unspecified+no_connect"))
    )
    (net (code "90") (name "unconnected-(U12-GPIO.3-Pad11)") (class "Default")
      (node (ref "U12") (pin "11") (pinfunction "GPIO.3_11") (pintype "unspecified+no_connect"))
    )
    (net (code "91") (name "unconnected-(U12-NC-Pad10)") (class "Default")
      (node (ref "U12") (pin "10") (pinfunction "NC_10") (pintype "unspecified+no_connect"))
    )
    (net (code "92") (name "unconnected-(U12-RI-Pad1)") (class "Default")
      (node (ref "U12") (pin "1") (pinfunction "RI_1") (pintype "unspecified+no_connect"))
    )
    (net (code "93") (name "unconnected-(U12-RST#-Pad9)") (class "Default")
      (node (ref "U12") (pin "9") (pinfunction "RST#_9") (pintype "unspecified+no_connect"))
    )
    (net (code "94") (name "unconnected-(U12-SUSPEND#-Pad15)") (class "Default")
      (node (ref "U12") (pin "15") (pinfunction "SUSPEND#_15") (pintype "unspecified+no_connect"))
    )
    (net (code "95") (name "unconnected-(U12-SUSPEND-Pad17)") (class "Default")
      (node (ref "U12") (pin "17") (pinfunction "SUSPEND_17") (pintype "unspecified+no_connect"))
    )
    (net (code "96") (name "unconnected-(U12-VPP-Pad16)") (class "Default")
      (node (ref "U12") (pin "16") (pinfunction "VPP_16") (pintype "unspecified+no_connect"))
    )
    (net (code "97") (name "unconnected-(U13-IO2-Pad24)") (class "Default")
      (node (ref "U13") (pin "24") (pinfunction "IO2_24") (pintype "unspecified+no_connect"))
    )
    (net (code "98") (name "unconnected-(U13-NC-Pad17)") (class "Default")
      (node (ref "U13") (pin "17") (pinfunction "NC_17") (pintype "unspecified+no_connect"))
    )
    (net (code "99") (name "unconnected-(U13-NC-Pad18)") (class "Default")
      (node (ref "U13") (pin "18") (pinfunction "NC_18") (pintype "unspecified+no_connect"))
    )
    (net (code "100") (name "unconnected-(U13-NC-Pad19)") (class "Default")
      (node (ref "U13") (pin "19") (pinfunction "NC_19") (pintype "unspecified+no_connect"))
    )
    (net (code "101") (name "unconnected-(U13-NC-Pad20)") (class "Default")
      (node (ref "U13") (pin "20") (pinfunction "NC_20") (pintype "unspecified+no_connect"))
    )
    (net (code "102") (name "unconnected-(U13-NC-Pad21)") (class "Default")
      (node (ref "U13") (pin "21") (pinfunction "NC_21") (pintype "unspecified+no_connect"))
    )
    (net (code "103") (name "unconnected-(U13-NC-Pad22)") (class "Default")
      (node (ref "U13") (pin "22") (pinfunction "NC_22") (pintype "unspecified+no_connect"))
    )
    (net (code "104") (name "unconnected-(U13-NC-Pad32)") (class "Default")
      (node (ref "U13") (pin "32") (pinfunction "NC_32") (pintype "unspecified+no_connect"))
    )
    (net (code "105") (name "unconnected-(USB4-SBU1-PadA8)") (class "Default")
      (node (ref "USB4") (pin "A8") (pinfunction "SBU1_A8") (pintype "bidirectional+no_connect"))
    )
    (net (code "106") (name "unconnected-(USB4-SBU2-PadB8)") (class "Default")
      (node (ref "USB4") (pin "B8") (pinfunction "SBU2_B8") (pintype "bidirectional+no_connect"))
    )
  )
)
